# drvinput1.net
KiCad netlist of a schematic drawn in Altium Designer
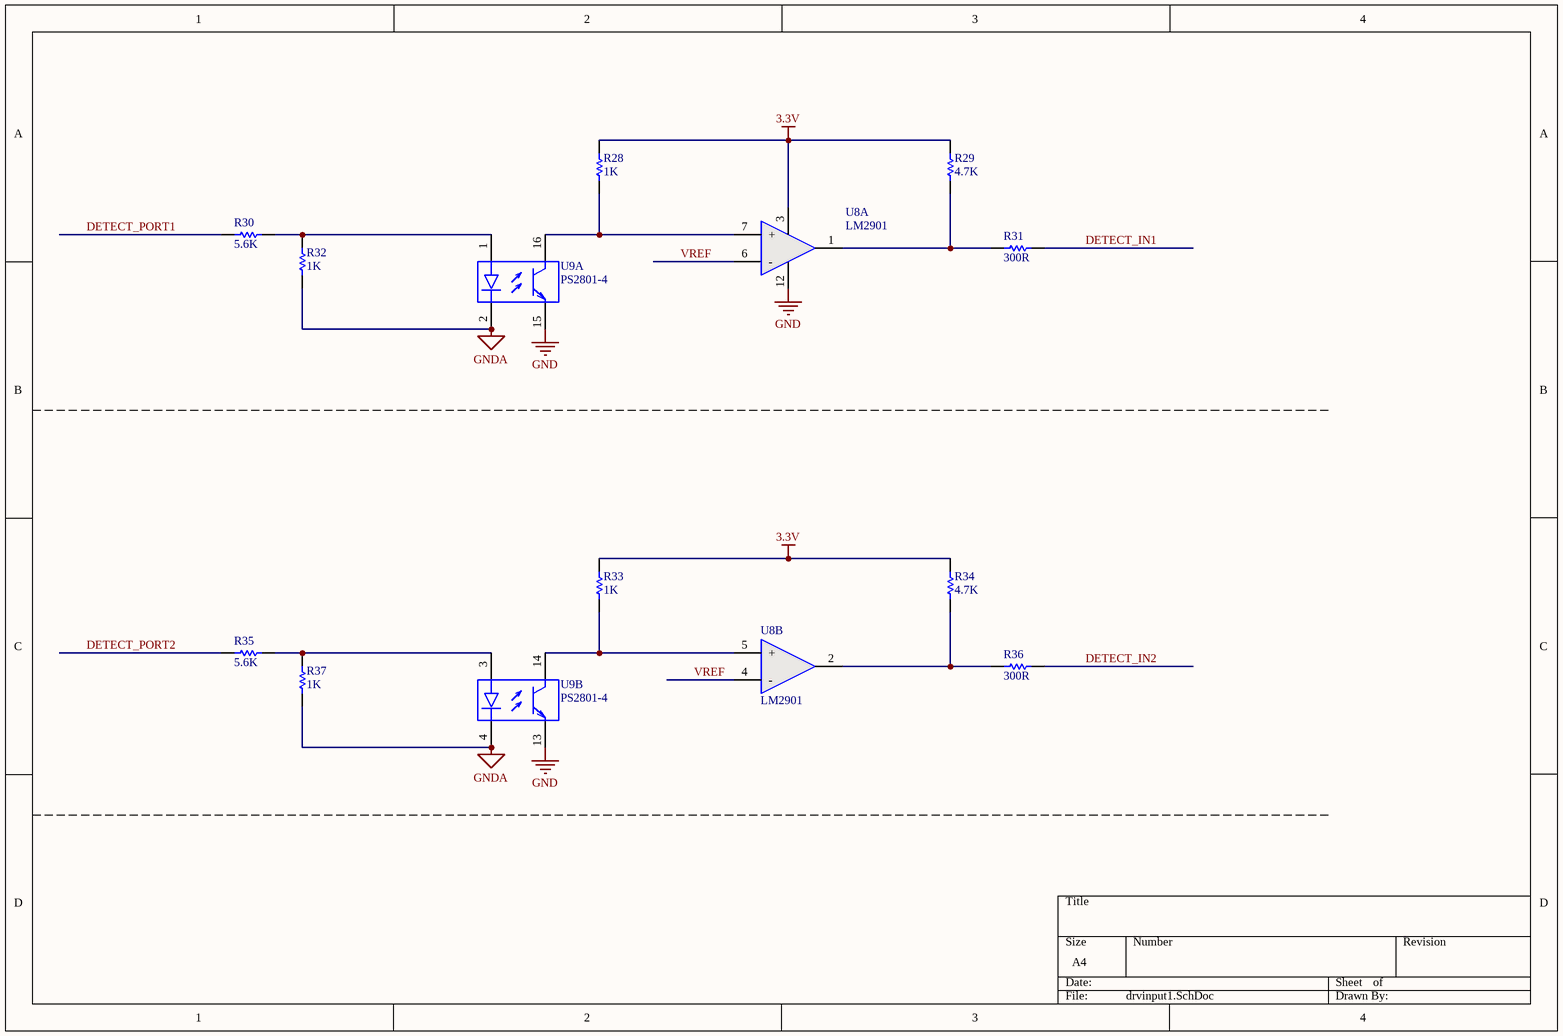
[diagram p0: drvinput1.SchDoc]

(export (version "E")
  (design (tool "Eeschema 10.0.6"))
  (components
    (comp (ref "R28")
      (value "1K")
      (footprint "RESC2012M")
      (description "Resistor")
      (fields (field (name "PUBLISHER") "Altium Limited"))
      (libsource (lib "Miscellaneous Devices") (part "Res1"))
    )
    (comp (ref "R29")
      (value "4.7K")
      (footprint "RESC2012M")
      (description "Resistor")
      (fields (field (name "PUBLISHER") "Altium Limited"))
      (libsource (lib "Miscellaneous Devices") (part "Res1"))
    )
    (comp (ref "R30")
      (value "5.6K")
      (footprint "RESC2012M")
      (description "Resistor")
      (fields (field (name "PUBLISHER") "Altium Limited"))
      (libsource (lib "Miscellaneous Devices") (part "Res1"))
    )
    (comp (ref "R31")
      (value "300R")
      (footprint "RESC2012M")
      (description "Resistor")
      (fields (field (name "PUBLISHER") "Altium Limited"))
      (libsource (lib "Miscellaneous Devices") (part "Res1"))
    )
    (comp (ref "R32")
      (value "1K")
      (footprint "RESC2012M")
      (description "Resistor")
      (fields (field (name "PUBLISHER") "Altium Limited"))
      (libsource (lib "Miscellaneous Devices") (part "Res1"))
    )
    (comp (ref "R33")
      (value "1K")
      (footprint "RESC2012M")
      (description "Resistor")
      (fields (field (name "PUBLISHER") "Altium Limited"))
      (libsource (lib "Miscellaneous Devices") (part "Res1"))
    )
    (comp (ref "R34")
      (value "4.7K")
      (footprint "RESC2012M")
      (description "Resistor")
      (fields (field (name "PUBLISHER") "Altium Limited"))
      (libsource (lib "Miscellaneous Devices") (part "Res1"))
    )
    (comp (ref "R35")
      (value "5.6K")
      (footprint "RESC2012M")
      (description "Resistor")
      (fields (field (name "PUBLISHER") "Altium Limited"))
      (libsource (lib "Miscellaneous Devices") (part "Res1"))
    )
    (comp (ref "R36")
      (value "300R")
      (footprint "RESC2012M")
      (description "Resistor")
      (fields (field (name "PUBLISHER") "Altium Limited"))
      (libsource (lib "Miscellaneous Devices") (part "Res1"))
    )
    (comp (ref "R37")
      (value "1K")
      (footprint "RESC2012M")
      (description "Resistor")
      (fields (field (name "PUBLISHER") "Altium Limited"))
      (libsource (lib "Miscellaneous Devices") (part "Res1"))
    )
    (comp (ref "U8")
      (value "LM2901")
      (footprint "SOIC-14AM")
      (description "4通道差分比较器芯片")
      (libsource (lib "UserSchDev") (part "LM2901"))
    )
    (comp (ref "U9")
      (value "PS2801-4")
      (footprint "SOIC16_N")
      (fields (field (name "PUBLISHER") "Altium Limited"))
      (libsource (lib "UserSchDev") (part "PS2801-4"))
    )
  )
  (nets
    (net (code "1") (name "/DETECT_IN1") (class "Default")
      (node (ref "R31") (pin "1") (pinfunction "1_1") (pintype "passive"))
    )
    (net (code "2") (name "/DETECT_IN2") (class "Default")
      (node (ref "R36") (pin "2") (pinfunction "2_2") (pintype "passive"))
    )
    (net (code "3") (name "/DETECT_PORT1") (class "Default")
      (node (ref "R30") (pin "2") (pinfunction "2_2") (pintype "passive"))
    )
    (net (code "4") (name "/DETECT_PORT2") (class "Default")
      (node (ref "R35") (pin "2") (pinfunction "2_2") (pintype "passive"))
    )
    (net (code "5") (name "/VREF") (class "Default")
      (node (ref "U8") (pin "4") (pinfunction "-_4") (pintype "passive"))
      (node (ref "U8") (pin "6") (pinfunction "-_6") (pintype "passive"))
    )
    (net (code "6") (name "3.3V") (class "Default")
      (node (ref "R28") (pin "1") (pinfunction "1_1") (pintype "passive"))
      (node (ref "R29") (pin "2") (pinfunction "2_2") (pintype "passive"))
      (node (ref "R33") (pin "1") (pinfunction "1_1") (pintype "passive"))
      (node (ref "R34") (pin "2") (pinfunction "2_2") (pintype "passive"))
      (node (ref "U8") (pin "3") (pinfunction "V+_3") (pintype "power_in"))
    )
    (net (code "7") (name "GND") (class "Default")
      (node (ref "U8") (pin "12") (pinfunction "V-_12") (pintype "power_in"))
      (node (ref "U9") (pin "13") (pinfunction "E_13") (pintype "passive"))
      (node (ref "U9") (pin "15") (pinfunction "E_15") (pintype "passive"))
    )
    (net (code "8") (name "GNDA") (class "Default")
      (node (ref "R32") (pin "1") (pinfunction "1_1") (pintype "passive"))
      (node (ref "R37") (pin "1") (pinfunction "1_1") (pintype "passive"))
      (node (ref "U9") (pin "2") (pinfunction "-_2") (pintype "passive"))
      (node (ref "U9") (pin "4") (pinfunction "-_4") (pintype "passive"))
    )
    (net (code "9") (name "Net-(U8A-+)") (class "Default")
      (node (ref "R28") (pin "2") (pinfunction "2_2") (pintype "passive"))
      (node (ref "U8") (pin "7") (pinfunction "+_7") (pintype "passive"))
      (node (ref "U9") (pin "16") (pinfunction "C_16") (pintype "passive"))
    )
    (net (code "10") (name "Net-(U8A-OUT)") (class "Default")
      (node (ref "R29") (pin "1") (pinfunction "1_1") (pintype "passive"))
      (node (ref "R31") (pin "2") (pinfunction "2_2") (pintype "passive"))
      (node (ref "U8") (pin "1") (pinfunction "OUT_1") (pintype "passive"))
    )
    (net (code "11") (name "Net-(U8B-+)") (class "Default")
      (node (ref "R33") (pin "2") (pinfunction "2_2") (pintype "passive"))
      (node (ref "U8") (pin "5") (pinfunction "+_5") (pintype "passive"))
      (node (ref "U9") (pin "14") (pinfunction "C_14") (pintype "passive"))
    )
    (net (code "12") (name "Net-(U8B-OUT)") (class "Default")
      (node (ref "R34") (pin "1") (pinfunction "1_1") (pintype "passive"))
      (node (ref "R36") (pin "1") (pinfunction "1_1") (pintype "passive"))
      (node (ref "U8") (pin "2") (pinfunction "OUT_2") (pintype "passive"))
    )
    (net (code "13") (name "Net-(U9A-+)") (class "Default")
      (node (ref "R30") (pin "1") (pinfunction "1_1") (pintype "passive"))
      (node (ref "R32") (pin "2") (pinfunction "2_2") (pintype "passive"))
      (node (ref "U9") (pin "1") (pinfunction "+_1") (pintype "passive"))
    )
    (net (code "14") (name "Net-(U9B-+)") (class "Default")
      (node (ref "R35") (pin "1") (pinfunction "1_1") (pintype "passive"))
      (node (ref "R37") (pin "2") (pinfunction "2_2") (pintype "passive"))
      (node (ref "U9") (pin "3") (pinfunction "+_3") (pintype "passive"))
    )
  )
)
